# front_light_via.net
KiCad netlist of a schematic drawn in EAGLE
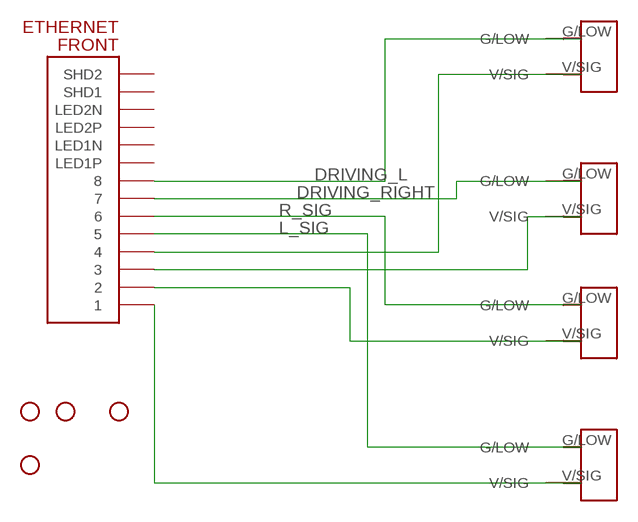
[diagram p0: schematic, sheet 1]

(export (version "E")
  (design (tool "Eeschema 10.0.6"))
  (components
    (comp (ref "FRONT")
      (value "ETHERNET")
      (footprint "eagle-import:A122645-ND")
      (libsource (lib "eagle-import") (part "ETHERNET"))
    )
    (comp (ref "H1")
      (value "STAND-OFF")
      (footprint "eagle-import:STAND-OFF")
      (libsource (lib "eagle-import") (part "STAND-OFF"))
    )
    (comp (ref "H2")
      (value "STAND-OFF")
      (footprint "eagle-import:STAND-OFF")
      (libsource (lib "eagle-import") (part "STAND-OFF"))
    )
    (comp (ref "H3")
      (value "STAND-OFF")
      (footprint "eagle-import:STAND-OFF")
      (libsource (lib "eagle-import") (part "STAND-OFF"))
    )
    (comp (ref "H4")
      (value "STAND-OFF")
      (footprint "eagle-import:STAND-OFF")
      (libsource (lib "eagle-import") (part "STAND-OFF"))
    )
    (comp (ref "U$1")
      (value "2_PIN_TECONNECTOR")
      (footprint "eagle-import:2_PIN_CONNECT")
      (libsource (lib "eagle-import") (part "2_PIN_TECONNECTOR"))
    )
    (comp (ref "U$2")
      (value "2_PIN_TECONNECTOR")
      (footprint "eagle-import:2_PIN_CONNECT")
      (libsource (lib "eagle-import") (part "2_PIN_TECONNECTOR"))
    )
    (comp (ref "U$3")
      (value "2_PIN_TECONNECTOR")
      (footprint "eagle-import:2_PIN_CONNECT")
      (libsource (lib "eagle-import") (part "2_PIN_TECONNECTOR"))
    )
    (comp (ref "U$4")
      (value "2_PIN_TECONNECTOR")
      (footprint "eagle-import:2_PIN_CONNECT")
      (libsource (lib "eagle-import") (part "2_PIN_TECONNECTOR"))
    )
  )
  (nets
    (net (code "1") (name "/DRIVING_L") (class "Default")
      (node (ref "FRONT") (pin "P$8") (pinfunction "8_P$8") (pintype "bidirectional"))
      (node (ref "U$1") (pin "G/LOW") (pinfunction "G/LOW_G/LOW") (pintype "bidirectional"))
    )
    (net (code "2") (name "/DRIVING_RIGHT") (class "Default")
      (node (ref "FRONT") (pin "P$7") (pinfunction "7_P$7") (pintype "bidirectional"))
      (node (ref "U$2") (pin "G/LOW") (pinfunction "G/LOW_G/LOW") (pintype "bidirectional"))
    )
    (net (code "3") (name "/L_SIG") (class "Default")
      (node (ref "FRONT") (pin "P$5") (pinfunction "5_P$5") (pintype "bidirectional"))
      (node (ref "U$4") (pin "G/LOW") (pinfunction "G/LOW_G/LOW") (pintype "bidirectional"))
    )
    (net (code "4") (name "/R_SIG") (class "Default")
      (node (ref "FRONT") (pin "P$6") (pinfunction "6_P$6") (pintype "bidirectional"))
      (node (ref "U$3") (pin "G/LOW") (pinfunction "G/LOW_G/LOW") (pintype "bidirectional"))
    )
    (net (code "5") (name "Net-(FRONT-1)") (class "Default")
      (node (ref "FRONT") (pin "P$1") (pinfunction "1_P$1") (pintype "bidirectional"))
      (node (ref "U$4") (pin "V/SIG") (pinfunction "V/SIG_V/SIG") (pintype "bidirectional"))
    )
    (net (code "6") (name "Net-(FRONT-2)") (class "Default")
      (node (ref "FRONT") (pin "P$2") (pinfunction "2_P$2") (pintype "bidirectional"))
      (node (ref "U$3") (pin "V/SIG") (pinfunction "V/SIG_V/SIG") (pintype "bidirectional"))
    )
    (net (code "7") (name "Net-(FRONT-3)") (class "Default")
      (node (ref "FRONT") (pin "P$3") (pinfunction "3_P$3") (pintype "bidirectional"))
      (node (ref "U$2") (pin "V/SIG") (pinfunction "V/SIG_V/SIG") (pintype "bidirectional"))
    )
    (net (code "8") (name "Net-(FRONT-4)") (class "Default")
      (node (ref "FRONT") (pin "P$4") (pinfunction "4_P$4") (pintype "bidirectional"))
      (node (ref "U$1") (pin "V/SIG") (pinfunction "V/SIG_V/SIG") (pintype "bidirectional"))
    )
    (net (code "9") (name "unconnected-(FRONT-LED1N-PadP$9)") (class "Default")
      (node (ref "FRONT") (pin "P$9") (pinfunction "LED1N_P$9") (pintype "bidirectional"))
    )
    (net (code "10") (name "unconnected-(FRONT-LED1P-PadP$10)") (class "Default")
      (node (ref "FRONT") (pin "P$10") (pinfunction "LED1P_P$10") (pintype "bidirectional"))
    )
    (net (code "11") (name "unconnected-(FRONT-LED2N-PadP$11)") (class "Default")
      (node (ref "FRONT") (pin "P$11") (pinfunction "LED2N_P$11") (pintype "bidirectional"))
    )
    (net (code "12") (name "unconnected-(FRONT-LED2P-PadP$12)") (class "Default")
      (node (ref "FRONT") (pin "P$12") (pinfunction "LED2P_P$12") (pintype "bidirectional"))
    )
    (net (code "13") (name "unconnected-(FRONT-SHD1-PadP$13)") (class "Default")
      (node (ref "FRONT") (pin "P$13") (pinfunction "SHD1_P$13") (pintype "bidirectional"))
    )
    (net (code "14") (name "unconnected-(FRONT-SHD2-PadP$14)") (class "Default")
      (node (ref "FRONT") (pin "P$14") (pinfunction "SHD2_P$14") (pintype "bidirectional"))
    )
  )
)
